# FrontPannel.net
KiCad netlist of a schematic drawn in Altium Designer
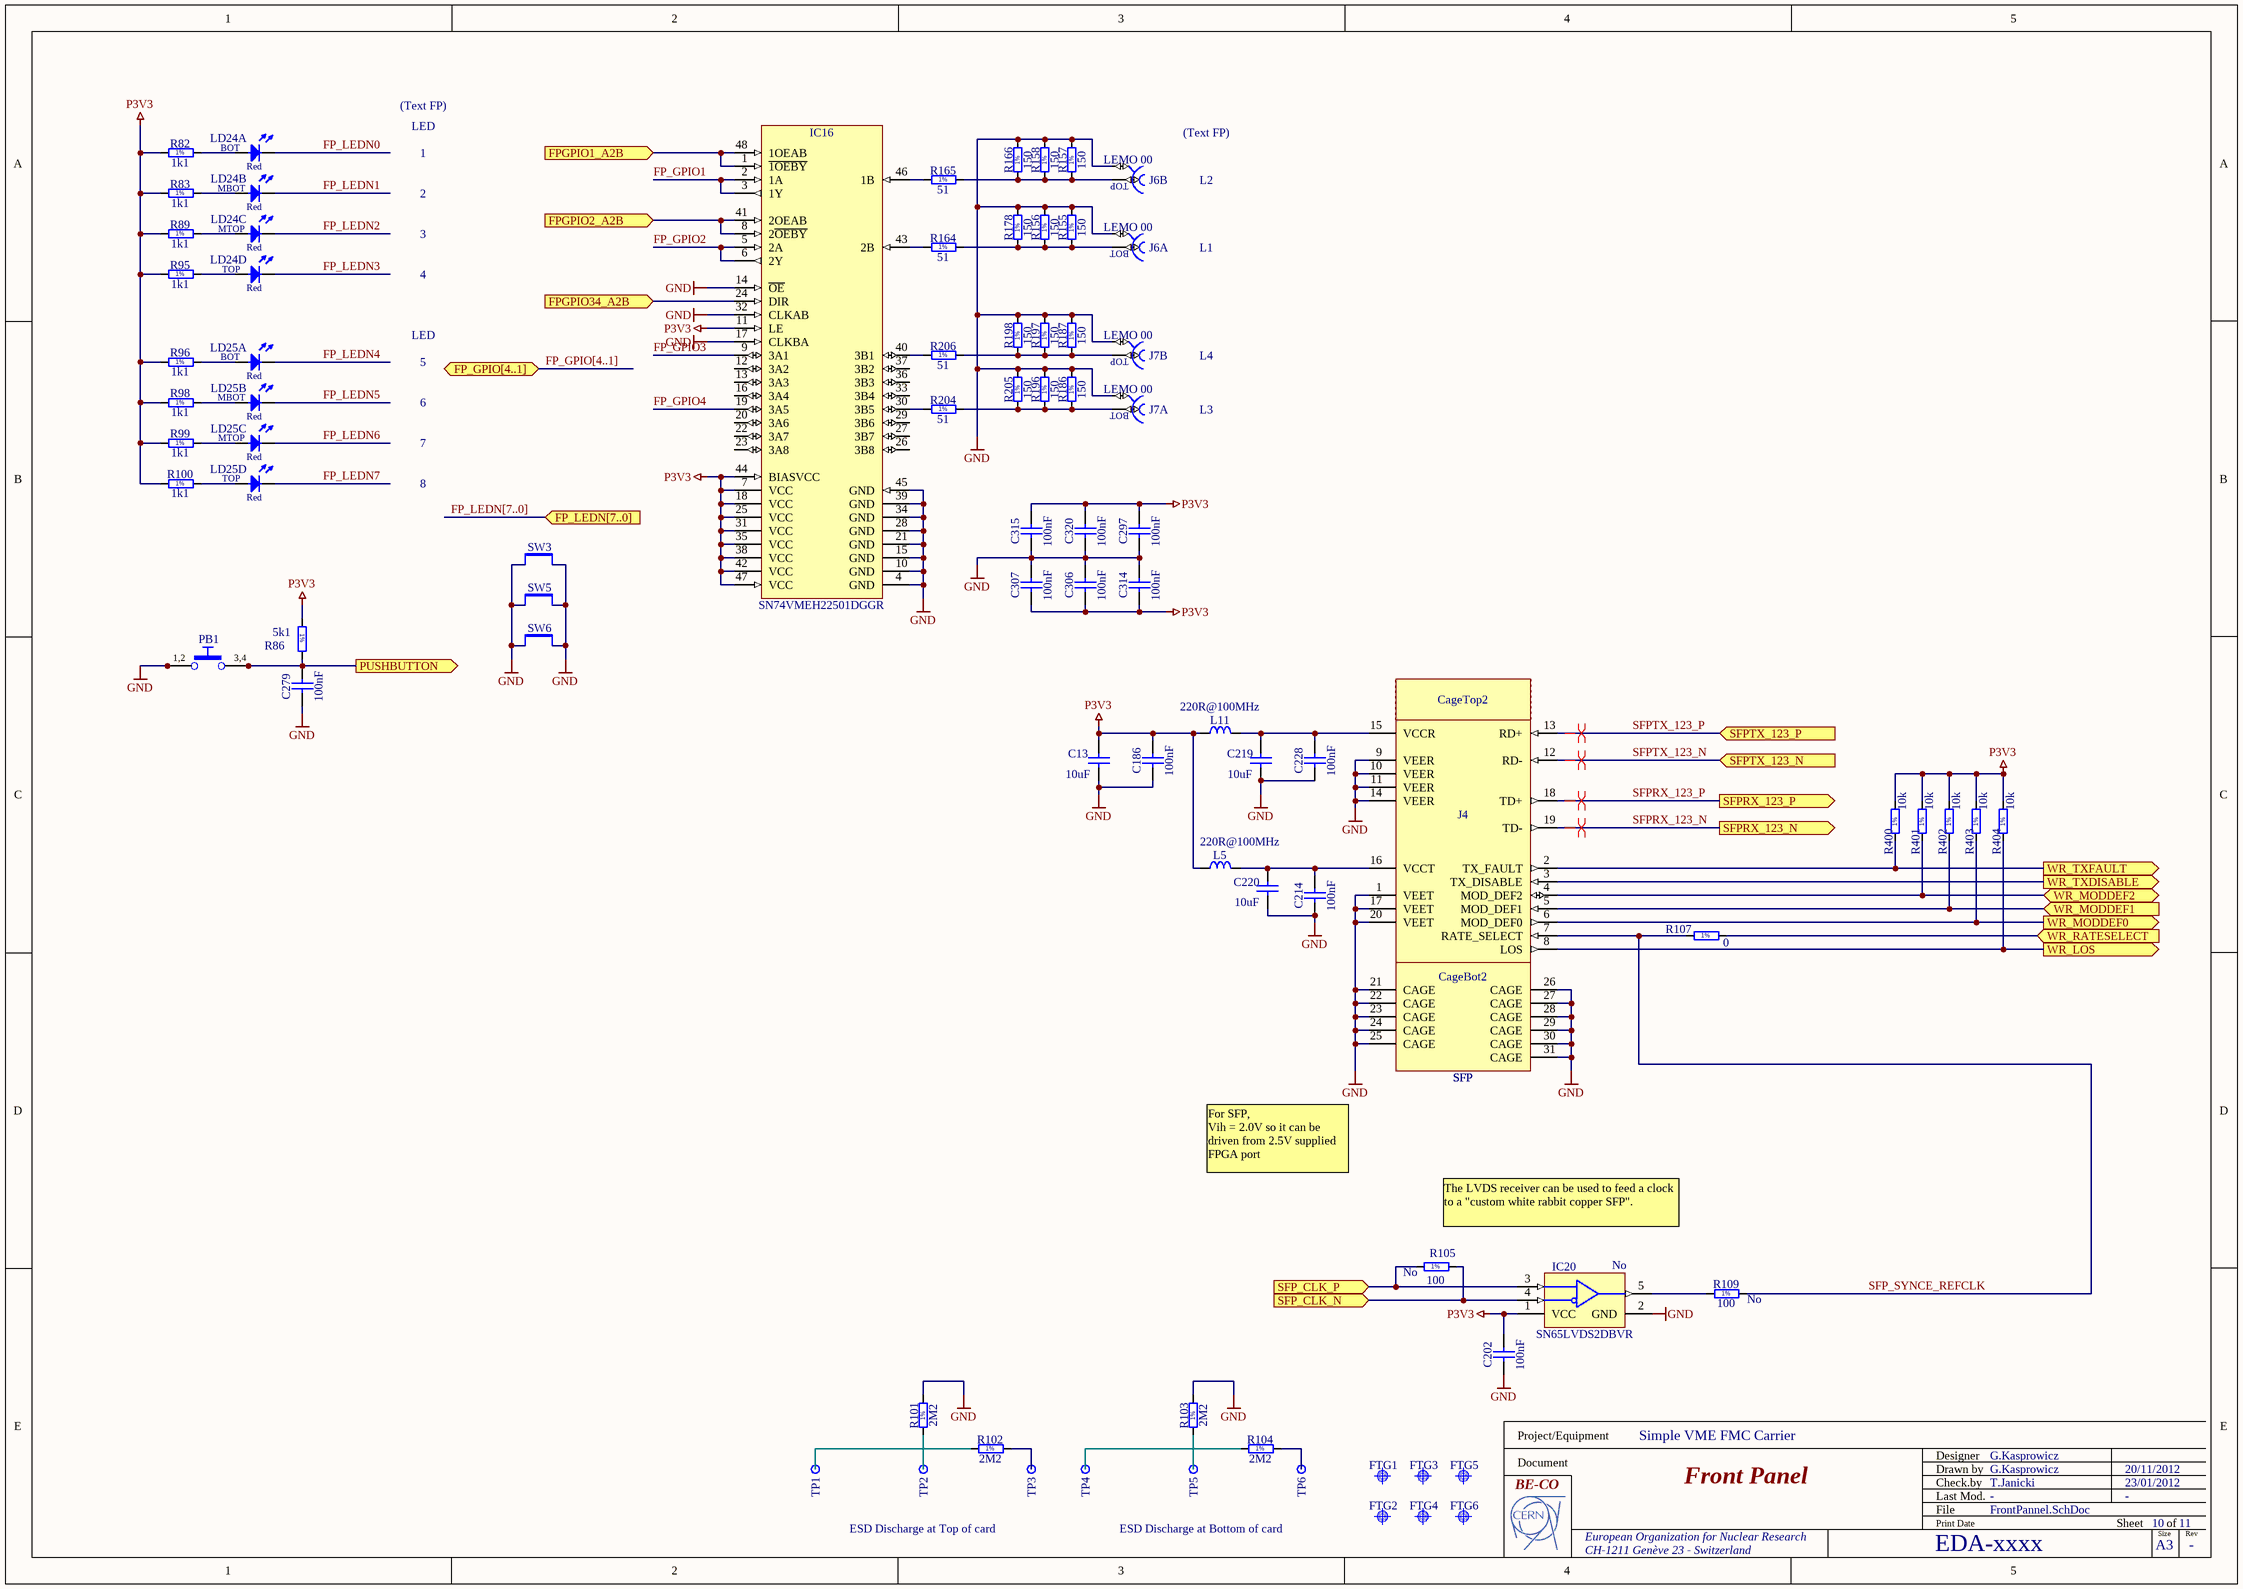
[diagram p0: FrontPannel.SchDoc]

(export (version "E")
  (design (tool "Eeschema 10.0.6"))
  (components
    (comp (ref "C13")
      (value "10uF")
      (footprint "CAPC3225X270N")
      (description "Non-polarised capacitor")
      (fields
        (field (name "PART NUMBER") "CC1210_10UF_25V_10%_X7R")
        (field (name "VOLTAGE") "25V")
        (field (name "AUTHOR") "CERN DEM JLC")
      )
      (libsource (lib "Capacitors") (part "Capacitor - non polarized"))
    )
    (comp (ref "C186")
      (value "100nF")
      (footprint "CAPC1005X55N")
      (description "Non-polarised capacitor")
      (fields
        (field (name "PART NUMBER") "CC0402_100NF_16V_10%_X7R")
        (field (name "VOLTAGE") "16V")
        (field (name "AUTHOR") "CERN DEM JLC")
      )
      (libsource (lib "Capacitors") (part "Capacitor - non polarized"))
    )
    (comp (ref "C202")
      (value "100nF")
      (footprint "CAPC1005X55N")
      (description "Non-polarised capacitor")
      (fields
        (field (name "PART NUMBER") "CC0402_100NF_16V_10%_X7R")
        (field (name "VOLTAGE") "16V")
        (field (name "AUTHOR") "CERN DEM JLC")
      )
      (libsource (lib "Capacitors") (part "Capacitor - non polarized"))
    )
    (comp (ref "C214")
      (value "100nF")
      (footprint "CAPC1005X55N")
      (description "Non-polarised capacitor")
      (fields
        (field (name "PART NUMBER") "CC0402_100NF_16V_10%_X7R")
        (field (name "VOLTAGE") "16V")
        (field (name "AUTHOR") "CERN DEM JLC")
      )
      (libsource (lib "Capacitors") (part "Capacitor - non polarized"))
    )
    (comp (ref "C219")
      (value "10uF")
      (footprint "CAPC3225X270N")
      (description "Non-polarised capacitor")
      (fields
        (field (name "PART NUMBER") "CC1210_10UF_25V_10%_X7R")
        (field (name "VOLTAGE") "25V")
        (field (name "AUTHOR") "CERN DEM JLC")
      )
      (libsource (lib "Capacitors") (part "Capacitor - non polarized"))
    )
    (comp (ref "C220")
      (value "10uF")
      (footprint "CAPC3225X270N")
      (description "Non-polarised capacitor")
      (fields
        (field (name "PART NUMBER") "CC1210_10UF_25V_10%_X7R")
        (field (name "VOLTAGE") "25V")
        (field (name "AUTHOR") "CERN DEM JLC")
      )
      (libsource (lib "Capacitors") (part "Capacitor - non polarized"))
    )
    (comp (ref "C228")
      (value "100nF")
      (footprint "CAPC1005X55N")
      (description "Non-polarised capacitor")
      (fields
        (field (name "PART NUMBER") "CC0402_100NF_16V_10%_X7R")
        (field (name "VOLTAGE") "16V")
        (field (name "AUTHOR") "CERN DEM JLC")
      )
      (libsource (lib "Capacitors") (part "Capacitor - non polarized"))
    )
    (comp (ref "C279")
      (value "100nF")
      (footprint "CAPC1005X55N")
      (description "Non-polarised capacitor")
      (fields
        (field (name "PART NUMBER") "CC0402_100NF_16V_10%_X7R")
        (field (name "VOLTAGE") "16V")
        (field (name "AUTHOR") "CERN DEM JLC")
      )
      (libsource (lib "Capacitors") (part "Capacitor - non polarized"))
    )
    (comp (ref "C297")
      (value "100nF")
      (footprint "CAPC1005X55N")
      (description "Non-polarised capacitor")
      (fields
        (field (name "PART NUMBER") "CC0402_100NF_16V_10%_X7R")
        (field (name "VOLTAGE") "16V")
        (field (name "AUTHOR") "CERN DEM JLC")
      )
      (libsource (lib "Capacitors") (part "Capacitor - non polarized"))
    )
    (comp (ref "C306")
      (value "100nF")
      (footprint "CAPC1005X55N")
      (description "Non-polarised capacitor")
      (fields
        (field (name "PART NUMBER") "CC0402_100NF_16V_10%_X7R")
        (field (name "VOLTAGE") "16V")
        (field (name "AUTHOR") "CERN DEM JLC")
      )
      (libsource (lib "Capacitors") (part "Capacitor - non polarized"))
    )
    (comp (ref "C307")
      (value "100nF")
      (footprint "CAPC1005X55N")
      (description "Non-polarised capacitor")
      (fields
        (field (name "PART NUMBER") "CC0402_100NF_16V_10%_X7R")
        (field (name "VOLTAGE") "16V")
        (field (name "AUTHOR") "CERN DEM JLC")
      )
      (libsource (lib "Capacitors") (part "Capacitor - non polarized"))
    )
    (comp (ref "C314")
      (value "100nF")
      (footprint "CAPC1005X55N")
      (description "Non-polarised capacitor")
      (fields
        (field (name "PART NUMBER") "CC0402_100NF_16V_10%_X7R")
        (field (name "VOLTAGE") "16V")
        (field (name "AUTHOR") "CERN DEM JLC")
      )
      (libsource (lib "Capacitors") (part "Capacitor - non polarized"))
    )
    (comp (ref "C315")
      (value "100nF")
      (footprint "CAPC1005X55N")
      (description "Non-polarised capacitor")
      (fields
        (field (name "PART NUMBER") "CC0402_100NF_16V_10%_X7R")
        (field (name "VOLTAGE") "16V")
        (field (name "AUTHOR") "CERN DEM JLC")
      )
      (libsource (lib "Capacitors") (part "Capacitor - non polarized"))
    )
    (comp (ref "C320")
      (value "100nF")
      (footprint "CAPC1005X55N")
      (description "Non-polarised capacitor")
      (fields
        (field (name "PART NUMBER") "CC0402_100NF_16V_10%_X7R")
        (field (name "VOLTAGE") "16V")
        (field (name "AUTHOR") "CERN DEM JLC")
      )
      (libsource (lib "Capacitors") (part "Capacitor - non polarized"))
    )
    (comp (ref "CageBot2")
      (value "SFP")
      (footprint "TYCO_6367034-1")
      (description "SFP  Cage Bottom (Small Form-factor Pluggable)")
      (fields
        (field (name "PART NUMBER") "TYCO_6367034-1")
        (field (name "MANUFACTURER") "TYCO ELECTRONICS")
        (field (name "AUTHOR") "CERN DEM JLC")
      )
      (libsource (lib "Connectors") (part "SFPx1_Cage Bottom"))
    )
    (comp (ref "CageTop2")
      (value "SFP")
      (footprint "TYCO_6367035-1")
      (description "SFP  Cage Top (Small Form-factor Pluggable)")
      (fields
        (field (name "PART NUMBER") "TYCO_6367035-1")
        (field (name "MANUFACTURER") "TYCO ELECTRONICS")
        (field (name "AUTHOR") "CERN DEM JLC")
      )
      (libsource (lib "Connectors") (part "SFPx1_Cage Top"))
    )
    (comp (ref "FTG1")
      (value "Use only in PCB")
      (footprint "FIDUCIAL_TOP_S100-200")
      (description "Fiducial Target")
      (fields (field (name "PART NUMBER") "FIDUCIAL_TARGET_S100-200") (field (name "AUTHOR") "CERN DEM JLC"))
      (libsource (lib "Eletro-mechanical") (part "Fiducial Target"))
    )
    (comp (ref "FTG2")
      (value "Use only in PCB")
      (footprint "FIDUCIAL_TOP_S100-200")
      (description "Fiducial Target")
      (fields (field (name "PART NUMBER") "FIDUCIAL_TARGET_S100-200") (field (name "AUTHOR") "CERN DEM JLC"))
      (libsource (lib "Eletro-mechanical") (part "Fiducial Target"))
    )
    (comp (ref "FTG3")
      (value "Use only in PCB")
      (footprint "FIDUCIAL_TOP_S100-200")
      (description "Fiducial Target")
      (fields (field (name "PART NUMBER") "FIDUCIAL_TARGET_S100-200") (field (name "AUTHOR") "CERN DEM JLC"))
      (libsource (lib "Eletro-mechanical") (part "Fiducial Target"))
    )
    (comp (ref "FTG4")
      (value "Use only in PCB")
      (footprint "FIDUCIAL_TOP_S100-200")
      (description "Fiducial Target")
      (fields (field (name "PART NUMBER") "FIDUCIAL_TARGET_S100-200") (field (name "AUTHOR") "CERN DEM JLC"))
      (libsource (lib "Eletro-mechanical") (part "Fiducial Target"))
    )
    (comp (ref "FTG5")
      (value "Use only in PCB")
      (footprint "FIDUCIAL_TOP_S100-200")
      (description "Fiducial Target")
      (fields (field (name "PART NUMBER") "FIDUCIAL_TARGET_S100-200") (field (name "AUTHOR") "CERN DEM JLC"))
      (libsource (lib "Eletro-mechanical") (part "Fiducial Target"))
    )
    (comp (ref "FTG6")
      (value "Use only in PCB")
      (footprint "FIDUCIAL_TOP_S100-200")
      (description "Fiducial Target")
      (fields (field (name "PART NUMBER") "FIDUCIAL_TARGET_S100-200") (field (name "AUTHOR") "CERN DEM JLC"))
      (libsource (lib "Eletro-mechanical") (part "Fiducial Target"))
    )
    (comp (ref "IC16")
      (value "SN74VMEH22501DGGR")
      (footprint "SOP50P810X120-48N")
      (description "8-Bit Universal Bus Transceiver and Two 1-Bit Bus Transceivers with 3-State Outputs")
      (fields (field (name "MANUFACTURER") "TEXAS INSTRUMENTS") (field (name "AUTHOR") "CERN DEM JLC"))
      (libsource (lib "ICs And Semiconductors") (part "74VMEH22501"))
    )
    (comp (ref "IC20")
      (value "SN65LVDS2DBVR")
      (footprint "SOT95P280X145-5N")
      (description "High-Speed Differential Line Receiver")
      (fields
        (field (name "MANUFACTURER") "TEXAS INSTRUMENTS")
        (field (name "MOUNTED") "No")
        (field (name "AUTHOR") "CERN DEM JLC")
      )
      (libsource (lib "ICs And Semiconductors") (part "SN65LVDS2DBVR"))
    )
    (comp (ref "J4")
      (value "SFP")
      (footprint "TYCO_1367073-1")
      (description "20 Position SFP  Connector (Small Form-factor Pluggable)")
      (fields
        (field (name "PART NUMBER") "TYCO_1367073-1")
        (field (name "MANUFACTURER") "TYCO ELECTRONICS")
        (field (name "AUTHOR") "CERN DEM JLC")
      )
      (libsource (lib "Connectors") (part "SFPx1"))
    )
    (comp (ref "J6")
      (value "LEMO 00")
      (footprint "LEMO_EPY.00.250.NTNY")
      (description "Dual Female Coax 1-2 Common Shield 3")
      (fields
        (field (name "PART NUMBER") "LEMO_EPY.00.250.NTNY")
        (field (name "MANUFACTURER") "LEMO")
        (field (name "AUTHOR") "CERN DEM JLC")
      )
      (libsource (lib "Connectors") (part "LEMO_EPY.00.250.NTN"))
    )
    (comp (ref "J7")
      (value "LEMO 00")
      (footprint "LEMO_EPY.00.250.NTNY")
      (description "Dual Female Coax 1-2 Common Shield 3")
      (fields
        (field (name "PART NUMBER") "LEMO_EPY.00.250.NTNY")
        (field (name "MANUFACTURER") "LEMO")
        (field (name "AUTHOR") "CERN DEM JLC")
      )
      (libsource (lib "Connectors") (part "LEMO_EPY.00.250.NTN"))
    )
    (comp (ref "L5")
      (value "220R@100MHz")
      (footprint "INDC2012X105N")
      (description "Inductor")
      (fields
        (field (name "PART NUMBER") "IND0805_MURATA_BLM21PG221SN1D")
        (field (name "POWER") "2A")
        (field (name "AUTHOR") "CERN DEM JLC")
      )
      (libsource (lib "Inductors & Transformers") (part "Inductor"))
    )
    (comp (ref "L11")
      (value "220R@100MHz")
      (footprint "INDC2012X105N")
      (description "Inductor")
      (fields
        (field (name "PART NUMBER") "IND0805_MURATA_BLM21PG221SN1D")
        (field (name "POWER") "2A")
        (field (name "AUTHOR") "CERN DEM JLC")
      )
      (libsource (lib "Inductors & Transformers") (part "Inductor"))
    )
    (comp (ref "LD24")
      (value "HE Red")
      (footprint "LED_BIVAR_H485CHDL")
      (description "LED x4 Red 1C2A-BOT_3C4A_5C6A_7C8A-TOP")
      (fields
        (field (name "PART NUMBER") "LED_BIVAR_H485CHDL")
        (field (name "MANUFACTURER") "BIVAR")
        (field (name "AUTHOR") "CERN DEM JLC")
      )
      (libsource (lib "ICs And Semiconductors") (part "LED x4 Red 1C2A-BOT_3C4A_5C6A_7C8A-TOP"))
    )
    (comp (ref "LD25")
      (value "HE Red")
      (footprint "LED_BIVAR_H485CHDL")
      (description "LED x4 Red 1C2A-BOT_3C4A_5C6A_7C8A-TOP")
      (fields
        (field (name "PART NUMBER") "LED_BIVAR_H485CHDL")
        (field (name "MANUFACTURER") "BIVAR")
        (field (name "AUTHOR") "CERN DEM JLC")
      )
      (libsource (lib "ICs And Semiconductors") (part "LED x4 Red 1C2A-BOT_3C4A_5C6A_7C8A-TOP"))
    )
    (comp (ref "PB1")
      (value "Push Button")
      (footprint "PB_TYCO_ALCOSWITCH_FSM2JSMA")
      (description "Push-Button Switch SPDT")
      (fields
        (field (name "PART NUMBER") "PB_TYCO_ALCOSWITCH_FSM2JSMA")
        (field (name "MANUFACTURER") "TYCO ALCOSWITCH")
        (field (name "AUTHOR") "CERN DEM JLC")
      )
      (libsource (lib "Eletro-mechanical") (part "PB SPST 12NO-34NO"))
    )
    (comp (ref "R82")
      (value "1k1")
      (footprint "RESC1608X55N")
      (description "Resistor - 1%")
      (fields
        (field (name "PART NUMBER") "R0603_1K1_1%_0.1W_100PPM")
        (field (name "POWER") "0.1W")
        (field (name "AUTHOR") "CERN DEM JLC")
      )
      (libsource (lib "Resistors") (part "Resistor - 1%"))
    )
    (comp (ref "R83")
      (value "1k1")
      (footprint "RESC1608X55N")
      (description "Resistor - 1%")
      (fields
        (field (name "PART NUMBER") "R0603_1K1_1%_0.1W_100PPM")
        (field (name "POWER") "0.1W")
        (field (name "AUTHOR") "CERN DEM JLC")
      )
      (libsource (lib "Resistors") (part "Resistor - 1%"))
    )
    (comp (ref "R86")
      (value "5k1")
      (footprint "RESC1608X55N")
      (description "Resistor - 1%")
      (fields
        (field (name "PART NUMBER") "R0603_5K1_1%_0.1W_100PPM")
        (field (name "POWER") "0.1W")
        (field (name "AUTHOR") "CERN DEM JLC")
      )
      (libsource (lib "Resistors") (part "Resistor - 1%"))
    )
    (comp (ref "R89")
      (value "1k1")
      (footprint "RESC1608X55N")
      (description "Resistor - 1%")
      (fields
        (field (name "PART NUMBER") "R0603_1K1_1%_0.1W_100PPM")
        (field (name "POWER") "0.1W")
        (field (name "AUTHOR") "CERN DEM JLC")
      )
      (libsource (lib "Resistors") (part "Resistor - 1%"))
    )
    (comp (ref "R95")
      (value "1k1")
      (footprint "RESC1608X55N")
      (description "Resistor - 1%")
      (fields
        (field (name "PART NUMBER") "R0603_1K1_1%_0.1W_100PPM")
        (field (name "POWER") "0.1W")
        (field (name "AUTHOR") "CERN DEM JLC")
      )
      (libsource (lib "Resistors") (part "Resistor - 1%"))
    )
    (comp (ref "R96")
      (value "1k1")
      (footprint "RESC1608X55N")
      (description "Resistor - 1%")
      (fields
        (field (name "PART NUMBER") "R0603_1K1_1%_0.1W_100PPM")
        (field (name "POWER") "0.1W")
        (field (name "AUTHOR") "CERN DEM JLC")
      )
      (libsource (lib "Resistors") (part "Resistor - 1%"))
    )
    (comp (ref "R98")
      (value "1k1")
      (footprint "RESC1608X55N")
      (description "Resistor - 1%")
      (fields
        (field (name "PART NUMBER") "R0603_1K1_1%_0.1W_100PPM")
        (field (name "POWER") "0.1W")
        (field (name "AUTHOR") "CERN DEM JLC")
      )
      (libsource (lib "Resistors") (part "Resistor - 1%"))
    )
    (comp (ref "R99")
      (value "1k1")
      (footprint "RESC1608X55N")
      (description "Resistor - 1%")
      (fields
        (field (name "PART NUMBER") "R0603_1K1_1%_0.1W_100PPM")
        (field (name "POWER") "0.1W")
        (field (name "AUTHOR") "CERN DEM JLC")
      )
      (libsource (lib "Resistors") (part "Resistor - 1%"))
    )
    (comp (ref "R100")
      (value "1k1")
      (footprint "RESC1608X55N")
      (description "Resistor - 1%")
      (fields
        (field (name "PART NUMBER") "R0603_1K1_1%_0.1W_100PPM")
        (field (name "POWER") "0.1W")
        (field (name "AUTHOR") "CERN DEM JLC")
      )
      (libsource (lib "Resistors") (part "Resistor - 1%"))
    )
    (comp (ref "R101")
      (value "2M2")
      (footprint "RESC2012X60N")
      (description "Resistor - 1%")
      (fields
        (field (name "PART NUMBER") "R0805_2M2_1%_0.125W_100PPM")
        (field (name "POWER") "0.125W")
        (field (name "AUTHOR") "CERN DEM JLC")
      )
      (libsource (lib "Resistors") (part "Resistor - 1%"))
    )
    (comp (ref "R102")
      (value "2M2")
      (footprint "RESC2012X60N")
      (description "Resistor - 1%")
      (fields
        (field (name "PART NUMBER") "R0805_2M2_1%_0.125W_100PPM")
        (field (name "POWER") "0.125W")
        (field (name "AUTHOR") "CERN DEM JLC")
      )
      (libsource (lib "Resistors") (part "Resistor - 1%"))
    )
    (comp (ref "R103")
      (value "2M2")
      (footprint "RESC2012X60N")
      (description "Resistor - 1%")
      (fields
        (field (name "PART NUMBER") "R0805_2M2_1%_0.125W_100PPM")
        (field (name "POWER") "0.125W")
        (field (name "AUTHOR") "CERN DEM JLC")
      )
      (libsource (lib "Resistors") (part "Resistor - 1%"))
    )
    (comp (ref "R104")
      (value "2M2")
      (footprint "RESC2012X60N")
      (description "Resistor - 1%")
      (fields
        (field (name "PART NUMBER") "R0805_2M2_1%_0.125W_100PPM")
        (field (name "POWER") "0.125W")
        (field (name "AUTHOR") "CERN DEM JLC")
      )
      (libsource (lib "Resistors") (part "Resistor - 1%"))
    )
    (comp (ref "R105")
      (value "100")
      (footprint "RESC1608X55N")
      (description "Resistor - 1%")
      (fields
        (field (name "PART NUMBER") "R0603_100R_1%_0.1W_100PPM")
        (field (name "POWER") "0.1W")
        (field (name "MOUNTED") "No")
        (field (name "AUTHOR") "CERN DEM JLC")
      )
      (libsource (lib "Resistors") (part "Resistor - 1%"))
    )
    (comp (ref "R107")
      (value "0")
      (footprint "RESC1608X55N")
      (description "Resistor - 1%")
      (fields
        (field (name "PART NUMBER") "R0603_0R_JUMPER")
        (field (name "MANUFACTURER") "GENERIC")
        (field (name "AUTHOR") "CERN DEM JLC")
      )
      (libsource (lib "Resistors") (part "Resistor - 1%"))
    )
    (comp (ref "R109")
      (value "100")
      (footprint "RESC1608X55N")
      (description "Resistor - 1%")
      (fields
        (field (name "PART NUMBER") "R0603_100R_1%_0.1W_100PPM")
        (field (name "POWER") "0.1W")
        (field (name "MOUNTED") "No")
        (field (name "AUTHOR") "CERN DEM JLC")
      )
      (libsource (lib "Resistors") (part "Resistor - 1%"))
    )
    (comp (ref "R155")
      (value "150")
      (footprint "RESC1005X40N")
      (description "Resistor - 1%")
      (fields
        (field (name "PART NUMBER") "R0402_150R_1%_0.0625W_100PPM")
        (field (name "POWER") "0.0625W")
        (field (name "AUTHOR") "CERN DEM JLC")
      )
      (libsource (lib "Resistors") (part "Resistor - 1%"))
    )
    (comp (ref "R156")
      (value "150")
      (footprint "RESC1005X40N")
      (description "Resistor - 1%")
      (fields
        (field (name "PART NUMBER") "R0402_150R_1%_0.0625W_100PPM")
        (field (name "POWER") "0.0625W")
        (field (name "AUTHOR") "CERN DEM JLC")
      )
      (libsource (lib "Resistors") (part "Resistor - 1%"))
    )
    (comp (ref "R157")
      (value "150")
      (footprint "RESC1005X40N")
      (description "Resistor - 1%")
      (fields
        (field (name "PART NUMBER") "R0402_150R_1%_0.0625W_100PPM")
        (field (name "POWER") "0.0625W")
        (field (name "AUTHOR") "CERN DEM JLC")
      )
      (libsource (lib "Resistors") (part "Resistor - 1%"))
    )
    (comp (ref "R158")
      (value "150")
      (footprint "RESC1005X40N")
      (description "Resistor - 1%")
      (fields
        (field (name "PART NUMBER") "R0402_150R_1%_0.0625W_100PPM")
        (field (name "POWER") "0.0625W")
        (field (name "AUTHOR") "CERN DEM JLC")
      )
      (libsource (lib "Resistors") (part "Resistor - 1%"))
    )
    (comp (ref "R164")
      (value "51")
      (footprint "RESC1005X40N")
      (description "Resistor - 1%")
      (fields
        (field (name "PART NUMBER") "R0402_51R_1%_0.0625W_100PPM")
        (field (name "POWER") "0.0625W")
        (field (name "AUTHOR") "CERN DEM JLC")
      )
      (libsource (lib "Resistors") (part "Resistor - 1%"))
    )
    (comp (ref "R165")
      (value "51")
      (footprint "RESC1005X40N")
      (description "Resistor - 1%")
      (fields
        (field (name "PART NUMBER") "R0402_51R_1%_0.0625W_100PPM")
        (field (name "POWER") "0.0625W")
        (field (name "AUTHOR") "CERN DEM JLC")
      )
      (libsource (lib "Resistors") (part "Resistor - 1%"))
    )
    (comp (ref "R166")
      (value "150")
      (footprint "RESC1005X40N")
      (description "Resistor - 1%")
      (fields
        (field (name "PART NUMBER") "R0402_150R_1%_0.0625W_100PPM")
        (field (name "POWER") "0.0625W")
        (field (name "AUTHOR") "CERN DEM JLC")
      )
      (libsource (lib "Resistors") (part "Resistor - 1%"))
    )
    (comp (ref "R178")
      (value "150")
      (footprint "RESC1005X40N")
      (description "Resistor - 1%")
      (fields
        (field (name "PART NUMBER") "R0402_150R_1%_0.0625W_100PPM")
        (field (name "POWER") "0.0625W")
        (field (name "AUTHOR") "CERN DEM JLC")
      )
      (libsource (lib "Resistors") (part "Resistor - 1%"))
    )
    (comp (ref "R186")
      (value "150")
      (footprint "RESC1005X40N")
      (description "Resistor - 1%")
      (fields
        (field (name "PART NUMBER") "R0402_150R_1%_0.0625W_100PPM")
        (field (name "POWER") "0.0625W")
        (field (name "AUTHOR") "CERN DEM JLC")
      )
      (libsource (lib "Resistors") (part "Resistor - 1%"))
    )
    (comp (ref "R187")
      (value "150")
      (footprint "RESC1005X40N")
      (description "Resistor - 1%")
      (fields
        (field (name "PART NUMBER") "R0402_150R_1%_0.0625W_100PPM")
        (field (name "POWER") "0.0625W")
        (field (name "AUTHOR") "CERN DEM JLC")
      )
      (libsource (lib "Resistors") (part "Resistor - 1%"))
    )
    (comp (ref "R196")
      (value "150")
      (footprint "RESC1005X40N")
      (description "Resistor - 1%")
      (fields
        (field (name "PART NUMBER") "R0402_150R_1%_0.0625W_100PPM")
        (field (name "POWER") "0.0625W")
        (field (name "AUTHOR") "CERN DEM JLC")
      )
      (libsource (lib "Resistors") (part "Resistor - 1%"))
    )
    (comp (ref "R197")
      (value "150")
      (footprint "RESC1005X40N")
      (description "Resistor - 1%")
      (fields
        (field (name "PART NUMBER") "R0402_150R_1%_0.0625W_100PPM")
        (field (name "POWER") "0.0625W")
        (field (name "AUTHOR") "CERN DEM JLC")
      )
      (libsource (lib "Resistors") (part "Resistor - 1%"))
    )
    (comp (ref "R198")
      (value "150")
      (footprint "RESC1005X40N")
      (description "Resistor - 1%")
      (fields
        (field (name "PART NUMBER") "R0402_150R_1%_0.0625W_100PPM")
        (field (name "POWER") "0.0625W")
        (field (name "AUTHOR") "CERN DEM JLC")
      )
      (libsource (lib "Resistors") (part "Resistor - 1%"))
    )
    (comp (ref "R204")
      (value "51")
      (footprint "RESC1005X40N")
      (description "Resistor - 1%")
      (fields
        (field (name "PART NUMBER") "R0402_51R_1%_0.0625W_100PPM")
        (field (name "POWER") "0.0625W")
        (field (name "AUTHOR") "CERN DEM JLC")
      )
      (libsource (lib "Resistors") (part "Resistor - 1%"))
    )
    (comp (ref "R205")
      (value "150")
      (footprint "RESC1005X40N")
      (description "Resistor - 1%")
      (fields
        (field (name "PART NUMBER") "R0402_150R_1%_0.0625W_100PPM")
        (field (name "POWER") "0.0625W")
        (field (name "AUTHOR") "CERN DEM JLC")
      )
      (libsource (lib "Resistors") (part "Resistor - 1%"))
    )
    (comp (ref "R206")
      (value "51")
      (footprint "RESC1005X40N")
      (description "Resistor - 1%")
      (fields
        (field (name "PART NUMBER") "R0402_51R_1%_0.0625W_100PPM")
        (field (name "POWER") "0.0625W")
        (field (name "AUTHOR") "CERN DEM JLC")
      )
      (libsource (lib "Resistors") (part "Resistor - 1%"))
    )
    (comp (ref "R400")
      (value "10k")
      (footprint "RESC1608X55N")
      (description "Resistor - 1%")
      (fields
        (field (name "PART NUMBER") "R0603_10K_1%_0.1W_100PPM")
        (field (name "POWER") "0.1W")
        (field (name "AUTHOR") "CERN DEM JLC")
      )
      (libsource (lib "Resistors") (part "Resistor - 1%"))
    )
    (comp (ref "R401")
      (value "10k")
      (footprint "RESC1608X55N")
      (description "Resistor - 1%")
      (fields
        (field (name "PART NUMBER") "R0603_10K_1%_0.1W_100PPM")
        (field (name "POWER") "0.1W")
        (field (name "AUTHOR") "CERN DEM JLC")
      )
      (libsource (lib "Resistors") (part "Resistor - 1%"))
    )
    (comp (ref "R402")
      (value "10k")
      (footprint "RESC1608X55N")
      (description "Resistor - 1%")
      (fields
        (field (name "PART NUMBER") "R0603_10K_1%_0.1W_100PPM")
        (field (name "POWER") "0.1W")
        (field (name "AUTHOR") "CERN DEM JLC")
      )
      (libsource (lib "Resistors") (part "Resistor - 1%"))
    )
    (comp (ref "R403")
      (value "10k")
      (footprint "RESC1608X55N")
      (description "Resistor - 1%")
      (fields
        (field (name "PART NUMBER") "R0603_10K_1%_0.1W_100PPM")
        (field (name "POWER") "0.1W")
        (field (name "AUTHOR") "CERN DEM JLC")
      )
      (libsource (lib "Resistors") (part "Resistor - 1%"))
    )
    (comp (ref "R404")
      (value "10k")
      (footprint "RESC1608X55N")
      (description "Resistor - 1%")
      (fields
        (field (name "PART NUMBER") "R0603_10K_1%_0.1W_100PPM")
        (field (name "POWER") "0.1W")
        (field (name "AUTHOR") "CERN DEM JLC")
      )
      (libsource (lib "Resistors") (part "Resistor - 1%"))
    )
    (comp (ref "SW3")
      (value "Jumper Type2")
      (footprint "COMATEL_313.0004.0.00.500")
      (description "Jumper 2 pins")
      (fields
        (field (name "PART NUMBER") "COMATEL_313.0004.0.00.500")
        (field (name "MANUFACTURER") "KONTEK COMATEL")
        (field (name "AUTHOR") "CERN DEM JMW")
      )
      (libsource (lib "Connectors") (part "Jumper Type2"))
    )
    (comp (ref "SW5")
      (value "Jumper Type2")
      (footprint "COMATEL_313.0004.0.00.500")
      (description "Jumper 2 pins")
      (fields
        (field (name "PART NUMBER") "COMATEL_313.0004.0.00.500")
        (field (name "MANUFACTURER") "KONTEK COMATEL")
        (field (name "AUTHOR") "CERN DEM JMW")
      )
      (libsource (lib "Connectors") (part "Jumper Type2"))
    )
    (comp (ref "SW6")
      (value "Jumper Type2")
      (footprint "COMATEL_313.0004.0.00.500")
      (description "Jumper 2 pins")
      (fields
        (field (name "PART NUMBER") "COMATEL_313.0004.0.00.500")
        (field (name "MANUFACTURER") "KONTEK COMATEL")
        (field (name "AUTHOR") "CERN DEM JMW")
      )
      (libsource (lib "Connectors") (part "Jumper Type2"))
    )
    (comp (ref "TP1")
      (value "Test Point")
      (footprint "TPS127")
      (fields (field (name "PART NUMBER") "SMD_PAD_1.27X1.27MM") (field (name "AUTHOR") "CERN DEM JLC"))
      (libsource (lib "Eletro-mechanical") (part "Test Point"))
    )
    (comp (ref "TP2")
      (value "Test Point")
      (footprint "TPS127")
      (fields (field (name "PART NUMBER") "SMD_PAD_1.27X1.27MM") (field (name "AUTHOR") "CERN DEM JLC"))
      (libsource (lib "Eletro-mechanical") (part "Test Point"))
    )
    (comp (ref "TP3")
      (value "Test Point")
      (footprint "TPS127")
      (fields (field (name "PART NUMBER") "SMD_PAD_1.27X1.27MM") (field (name "AUTHOR") "CERN DEM JLC"))
      (libsource (lib "Eletro-mechanical") (part "Test Point"))
    )
    (comp (ref "TP4")
      (value "Test Point")
      (footprint "TPS127")
      (fields (field (name "PART NUMBER") "SMD_PAD_1.27X1.27MM") (field (name "AUTHOR") "CERN DEM JLC"))
      (libsource (lib "Eletro-mechanical") (part "Test Point"))
    )
    (comp (ref "TP5")
      (value "Test Point")
      (footprint "TPS127")
      (fields (field (name "PART NUMBER") "SMD_PAD_1.27X1.27MM") (field (name "AUTHOR") "CERN DEM JLC"))
      (libsource (lib "Eletro-mechanical") (part "Test Point"))
    )
    (comp (ref "TP6")
      (value "Test Point")
      (footprint "TPS127")
      (fields (field (name "PART NUMBER") "SMD_PAD_1.27X1.27MM") (field (name "AUTHOR") "CERN DEM JLC"))
      (libsource (lib "Eletro-mechanical") (part "Test Point"))
    )
  )
  (nets
    (net (code "1") (name "/FPGPIO1_A2B") (class "Default")
      (node (ref "IC16") (pin "1") (pinfunction "~{1OEBY}_1") (pintype "input"))
      (node (ref "IC16") (pin "48") (pinfunction "1OEAB_48") (pintype "input"))
    )
    (net (code "2") (name "/FPGPIO2_A2B") (class "Default")
      (node (ref "IC16") (pin "41") (pinfunction "2OEAB_41") (pintype "input"))
      (node (ref "IC16") (pin "8") (pinfunction "2~{OEBY}_8") (pintype "input"))
    )
    (net (code "3") (name "/FPGPIO34_A2B") (class "Default")
      (node (ref "IC16") (pin "24") (pinfunction "DIR_24") (pintype "input"))
    )
    (net (code "4") (name "/FP_GPIO1") (class "Default")
      (node (ref "IC16") (pin "2") (pinfunction "1A_2") (pintype "input"))
      (node (ref "IC16") (pin "3") (pinfunction "1Y_3") (pintype "output"))
    )
    (net (code "5") (name "/FP_GPIO2") (class "Default")
      (node (ref "IC16") (pin "5") (pinfunction "2A_5") (pintype "input"))
      (node (ref "IC16") (pin "6") (pinfunction "2Y_6") (pintype "output"))
    )
    (net (code "6") (name "/FP_GPIO3") (class "Default")
      (node (ref "IC16") (pin "9") (pinfunction "3A1_9") (pintype "bidirectional"))
    )
    (net (code "7") (name "/FP_GPIO4") (class "Default")
      (node (ref "IC16") (pin "19") (pinfunction "3A5_19") (pintype "bidirectional"))
    )
    (net (code "9") (name "/FP_LEDN0") (class "Default")
      (node (ref "LD24") (pin "1") (pinfunction "C_1") (pintype "passive"))
    )
    (net (code "10") (name "/FP_LEDN1") (class "Default")
      (node (ref "LD24") (pin "3") (pinfunction "C_3") (pintype "passive"))
    )
    (net (code "11") (name "/FP_LEDN2") (class "Default")
      (node (ref "LD24") (pin "5") (pinfunction "C_5") (pintype "passive"))
    )
    (net (code "12") (name "/FP_LEDN3") (class "Default")
      (node (ref "LD24") (pin "7") (pinfunction "C_7") (pintype "passive"))
    )
    (net (code "13") (name "/FP_LEDN4") (class "Default")
      (node (ref "LD25") (pin "1") (pinfunction "C_1") (pintype "passive"))
    )
    (net (code "14") (name "/FP_LEDN5") (class "Default")
      (node (ref "LD25") (pin "3") (pinfunction "C_3") (pintype "passive"))
    )
    (net (code "15") (name "/FP_LEDN6") (class "Default")
      (node (ref "LD25") (pin "5") (pinfunction "C_5") (pintype "passive"))
    )
    (net (code "16") (name "/FP_LEDN7") (class "Default")
      (node (ref "LD25") (pin "7") (pinfunction "C_7") (pintype "passive"))
    )
    (net (code "18") (name "/PUSHBUTTON") (class "Default")
      (node (ref "C279") (pin "2") (pinfunction "2_2") (pintype "passive"))
      (node (ref "PB1") (pin "3") (pinfunction "3_3") (pintype "passive"))
      (node (ref "PB1") (pin "4") (pinfunction "4_4") (pintype "passive"))
      (node (ref "R86") (pin "2") (pinfunction "2_2") (pintype "passive"))
    )
    (net (code "19") (name "/SFPRX_123_N") (class "Default")
      (node (ref "J4") (pin "19") (pinfunction "TD-_19") (pintype "output"))
    )
    (net (code "20") (name "/SFPRX_123_P") (class "Default")
      (node (ref "J4") (pin "18") (pinfunction "TD+_18") (pintype "output"))
    )
    (net (code "21") (name "/SFPTX_123_N") (class "Default")
      (node (ref "J4") (pin "12") (pinfunction "RD-_12") (pintype "input"))
    )
    (net (code "22") (name "/SFPTX_123_P") (class "Default")
      (node (ref "J4") (pin "13") (pinfunction "RD+_13") (pintype "input"))
    )
    (net (code "23") (name "/SFP_CLK_N") (class "Default")
      (node (ref "IC20") (pin "4") (pinfunction "B_4") (pintype "input"))
      (node (ref "R105") (pin "2") (pinfunction "2_2") (pintype "passive"))
    )
    (net (code "24") (name "/SFP_CLK_P") (class "Default")
      (node (ref "IC20") (pin "3") (pinfunction "A_3") (pintype "input"))
      (node (ref "R105") (pin "1") (pinfunction "1_1") (pintype "passive"))
    )
    (net (code "25") (name "/SFP_SYNCE_REFCLK") (class "Default")
      (node (ref "J4") (pin "7") (pinfunction "RATE_SELECT_7") (pintype "input"))
      (node (ref "R107") (pin "1") (pinfunction "1_1") (pintype "passive"))
      (node (ref "R109") (pin "2") (pinfunction "2_2") (pintype "passive"))
    )
    (net (code "26") (name "/WR_LOS") (class "Default")
      (node (ref "J4") (pin "8") (pinfunction "LOS_8") (pintype "output"))
      (node (ref "R404") (pin "1") (pinfunction "1_1") (pintype "passive"))
    )
    (net (code "27") (name "/WR_MODDEF0") (class "Default")
      (node (ref "J4") (pin "6") (pinfunction "MOD_DEF0_6") (pintype "output"))
      (node (ref "R403") (pin "1") (pinfunction "1_1") (pintype "passive"))
    )
    (net (code "28") (name "/WR_MODDEF1") (class "Default")
      (node (ref "J4") (pin "5") (pinfunction "MOD_DEF1_5") (pintype "input"))
      (node (ref "R402") (pin "1") (pinfunction "1_1") (pintype "passive"))
    )
    (net (code "29") (name "/WR_MODDEF2") (class "Default")
      (node (ref "J4") (pin "4") (pinfunction "MOD_DEF2_4") (pintype "bidirectional"))
      (node (ref "R401") (pin "1") (pinfunction "1_1") (pintype "passive"))
    )
    (net (code "30") (name "/WR_RATESELECT") (class "Default")
      (node (ref "R107") (pin "2") (pinfunction "2_2") (pintype "passive"))
    )
    (net (code "31") (name "/WR_TXDISABLE") (class "Default")
      (node (ref "J4") (pin "3") (pinfunction "TX_DISABLE_3") (pintype "input"))
    )
    (net (code "32") (name "/WR_TXFAULT") (class "Default")
      (node (ref "J4") (pin "2") (pinfunction "TX_FAULT_2") (pintype "output"))
      (node (ref "R400") (pin "1") (pinfunction "1_1") (pintype "passive"))
    )
    (net (code "33") (name "GND") (class "Default")
      (node (ref "C13") (pin "2") (pinfunction "2_2") (pintype "passive"))
      (node (ref "C186") (pin "2") (pinfunction "2_2") (pintype "passive"))
      (node (ref "C202") (pin "1") (pinfunction "1_1") (pintype "passive"))
      (node (ref "C214") (pin "2") (pinfunction "2_2") (pintype "passive"))
      (node (ref "C219") (pin "2") (pinfunction "2_2") (pintype "passive"))
      (node (ref "C220") (pin "2") (pinfunction "2_2") (pintype "passive"))
      (node (ref "C228") (pin "2") (pinfunction "2_2") (pintype "passive"))
      (node (ref "C279") (pin "1") (pinfunction "1_1") (pintype "passive"))
      (node (ref "C297") (pin "1") (pinfunction "1_1") (pintype "passive"))
      (node (ref "C306") (pin "2") (pinfunction "2_2") (pintype "passive"))
      (node (ref "C307") (pin "2") (pinfunction "2_2") (pintype "passive"))
      (node (ref "C314") (pin "2") (pinfunction "2_2") (pintype "passive"))
      (node (ref "C315") (pin "1") (pinfunction "1_1") (pintype "passive"))
      (node (ref "C320") (pin "1") (pinfunction "1_1") (pintype "passive"))
      (node (ref "CageBot2") (pin "21") (pinfunction "CAGE_21") (pintype "power_in"))
      (node (ref "CageBot2") (pin "22") (pinfunction "CAGE_22") (pintype "power_in"))
      (node (ref "CageBot2") (pin "23") (pinfunction "CAGE_23") (pintype "power_in"))
      (node (ref "CageBot2") (pin "24") (pinfunction "CAGE_24") (pintype "power_in"))
      (node (ref "CageBot2") (pin "25") (pinfunction "CAGE_25") (pintype "power_in"))
      (node (ref "CageBot2") (pin "26") (pinfunction "CAGE_26") (pintype "power_in"))
      (node (ref "CageBot2") (pin "27") (pinfunction "CAGE_27") (pintype "power_in"))
      (node (ref "CageBot2") (pin "28") (pinfunction "CAGE_28") (pintype "power_in"))
      (node (ref "CageBot2") (pin "29") (pinfunction "CAGE_29") (pintype "power_in"))
      (node (ref "CageBot2") (pin "30") (pinfunction "CAGE_30") (pintype "power_in"))
      (node (ref "CageBot2") (pin "31") (pinfunction "CAGE_31") (pintype "power_in"))
      (node (ref "IC16") (pin "10") (pinfunction "GND_10") (pintype "power_in"))
      (node (ref "IC16") (pin "14") (pinfunction "~{OE}_14") (pintype "input"))
      (node (ref "IC16") (pin "15") (pinfunction "GND_15") (pintype "power_in"))
      (node (ref "IC16") (pin "17") (pinfunction "CLKBA_17") (pintype "input"))
      (node (ref "IC16") (pin "21") (pinfunction "GND_21") (pintype "power_in"))
      (node (ref "IC16") (pin "28") (pinfunction "GND_28") (pintype "power_in"))
      (node (ref "IC16") (pin "32") (pinfunction "CLKAB_32") (pintype "input"))
      (node (ref "IC16") (pin "34") (pinfunction "GND_34") (pintype "power_in"))
      (node (ref "IC16") (pin "39") (pinfunction "GND_39") (pintype "power_in"))
      (node (ref "IC16") (pin "4") (pinfunction "GND_4") (pintype "power_in"))
      (node (ref "IC16") (pin "45") (pinfunction "GND_45") (pintype "input"))
      (node (ref "IC20") (pin "2") (pinfunction "GND_2") (pintype "power_in"))
      (node (ref "J4") (pin "1") (pinfunction "VEET_1") (pintype "power_in"))
      (node (ref "J4") (pin "10") (pinfunction "VEER_10") (pintype "power_in"))
      (node (ref "J4") (pin "11") (pinfunction "VEER_11") (pintype "power_in"))
      (node (ref "J4") (pin "14") (pinfunction "VEER_14") (pintype "power_in"))
      (node (ref "J4") (pin "17") (pinfunction "VEET_17") (pintype "power_in"))
      (node (ref "J4") (pin "20") (pinfunction "VEET_20") (pintype "power_in"))
      (node (ref "J4") (pin "9") (pinfunction "VEER_9") (pintype "power_in"))
      (node (ref "J6") (pin "3") (pinfunction "3_3") (pintype "bidirectional"))
      (node (ref "J7") (pin "3") (pinfunction "3_3") (pintype "bidirectional"))
      (node (ref "PB1") (pin "1") (pinfunction "1_1") (pintype "passive"))
      (node (ref "PB1") (pin "2") (pinfunction "2_2") (pintype "passive"))
      (node (ref "R101") (pin "2") (pinfunction "2_2") (pintype "passive"))
      (node (ref "R103") (pin "2") (pinfunction "2_2") (pintype "passive"))
      (node (ref "R155") (pin "2") (pinfunction "2_2") (pintype "passive"))
      (node (ref "R156") (pin "2") (pinfunction "2_2") (pintype "passive"))
      (node (ref "R157") (pin "2") (pinfunction "2_2") (pintype "passive"))
      (node (ref "R158") (pin "2") (pinfunction "2_2") (pintype "passive"))
      (node (ref "R166") (pin "2") (pinfunction "2_2") (pintype "passive"))
      (node (ref "R178") (pin "2") (pinfunction "2_2") (pintype "passive"))
      (node (ref "R186") (pin "2") (pinfunction "2_2") (pintype "passive"))
      (node (ref "R187") (pin "2") (pinfunction "2_2") (pintype "passive"))
      (node (ref "R196") (pin "2") (pinfunction "2_2") (pintype "passive"))
      (node (ref "R197") (pin "2") (pinfunction "2_2") (pintype "passive"))
      (node (ref "R198") (pin "2") (pinfunction "2_2") (pintype "passive"))
      (node (ref "R205") (pin "2") (pinfunction "2_2") (pintype "passive"))
      (node (ref "SW3") (pin "1") (pinfunction "1_1") (pintype "bidirectional"))
      (node (ref "SW3") (pin "2") (pinfunction "2_2") (pintype "bidirectional"))
      (node (ref "SW5") (pin "1") (pinfunction "1_1") (pintype "bidirectional"))
      (node (ref "SW5") (pin "2") (pinfunction "2_2") (pintype "bidirectional"))
      (node (ref "SW6") (pin "1") (pinfunction "1_1") (pintype "bidirectional"))
      (node (ref "SW6") (pin "2") (pinfunction "2_2") (pintype "bidirectional"))
    )
    (net (code "34") (name "Net-(IC16-1B)") (class "Default")
      (node (ref "IC16") (pin "46") (pinfunction "1B_46") (pintype "input"))
      (node (ref "R165") (pin "1") (pinfunction "1_1") (pintype "passive"))
    )
    (net (code "35") (name "Net-(IC16-2B)") (class "Default")
      (node (ref "IC16") (pin "43") (pinfunction "2B_43") (pintype "input"))
      (node (ref "R164") (pin "1") (pinfunction "1_1") (pintype "passive"))
    )
    (net (code "36") (name "Net-(IC16-3B1)") (class "Default")
      (node (ref "IC16") (pin "40") (pinfunction "3B1_40") (pintype "bidirectional"))
      (node (ref "R206") (pin "1") (pinfunction "1_1") (pintype "passive"))
    )
    (net (code "37") (name "Net-(IC16-3B5)") (class "Default")
      (node (ref "IC16") (pin "30") (pinfunction "3B5_30") (pintype "bidirectional"))
      (node (ref "R204") (pin "1") (pinfunction "1_1") (pintype "passive"))
    )
    (net (code "38") (name "Net-(IC20-R)") (class "Default")
      (node (ref "IC20") (pin "5") (pinfunction "R_5") (pintype "output"))
      (node (ref "R109") (pin "1") (pinfunction "1_1") (pintype "passive"))
    )
    (net (code "39") (name "Net-(J4-VCCR)") (class "Default")
      (node (ref "C219") (pin "1") (pinfunction "1_1") (pintype "passive"))
      (node (ref "C228") (pin "1") (pinfunction "1_1") (pintype "passive"))
      (node (ref "J4") (pin "15") (pinfunction "VCCR_15") (pintype "power_in"))
      (node (ref "L11") (pin "2") (pinfunction "2_2") (pintype "passive"))
    )
    (net (code "40") (name "Net-(J4-VCCT)") (class "Default")
      (node (ref "C214") (pin "1") (pinfunction "1_1") (pintype "passive"))
      (node (ref "C220") (pin "1") (pinfunction "1_1") (pintype "passive"))
      (node (ref "J4") (pin "16") (pinfunction "VCCT_16") (pintype "power_in"))
      (node (ref "L5") (pin "2") (pinfunction "2_2") (pintype "passive"))
    )
    (net (code "41") (name "Net-(J6-Pad1)") (class "Default")
      (node (ref "J6") (pin "1") (pinfunction "1_1") (pintype "bidirectional"))
      (node (ref "R155") (pin "1") (pinfunction "1_1") (pintype "passive"))
      (node (ref "R156") (pin "1") (pinfunction "1_1") (pintype "passive"))
      (node (ref "R164") (pin "2") (pinfunction "2_2") (pintype "passive"))
      (node (ref "R178") (pin "1") (pinfunction "1_1") (pintype "passive"))
    )
    (net (code "42") (name "Net-(J6-Pad2)") (class "Default")
      (node (ref "J6") (pin "2") (pinfunction "2_2") (pintype "bidirectional"))
      (node (ref "R157") (pin "1") (pinfunction "1_1") (pintype "passive"))
      (node (ref "R158") (pin "1") (pinfunction "1_1") (pintype "passive"))
      (node (ref "R165") (pin "2") (pinfunction "2_2") (pintype "passive"))
      (node (ref "R166") (pin "1") (pinfunction "1_1") (pintype "passive"))
    )
    (net (code "43") (name "Net-(J7-Pad1)") (class "Default")
      (node (ref "J7") (pin "1") (pinfunction "1_1") (pintype "bidirectional"))
      (node (ref "R186") (pin "1") (pinfunction "1_1") (pintype "passive"))
      (node (ref "R196") (pin "1") (pinfunction "1_1") (pintype "passive"))
      (node (ref "R204") (pin "2") (pinfunction "2_2") (pintype "passive"))
      (node (ref "R205") (pin "1") (pinfunction "1_1") (pintype "passive"))
    )
    (net (code "44") (name "Net-(J7-Pad2)") (class "Default")
      (node (ref "J7") (pin "2") (pinfunction "2_2") (pintype "bidirectional"))
      (node (ref "R187") (pin "1") (pinfunction "1_1") (pintype "passive"))
      (node (ref "R197") (pin "1") (pinfunction "1_1") (pintype "passive"))
      (node (ref "R198") (pin "1") (pinfunction "1_1") (pintype "passive"))
      (node (ref "R206") (pin "2") (pinfunction "2_2") (pintype "passive"))
    )
    (net (code "45") (name "Net-(LD24A-A)") (class "Default")
      (node (ref "LD24") (pin "2") (pinfunction "A_2") (pintype "passive"))
      (node (ref "R82") (pin "2") (pinfunction "2_2") (pintype "passive"))
    )
    (net (code "46") (name "Net-(LD24B-A)") (class "Default")
      (node (ref "LD24") (pin "4") (pinfunction "A_4") (pintype "passive"))
      (node (ref "R83") (pin "2") (pinfunction "2_2") (pintype "passive"))
    )
    (net (code "47") (name "Net-(LD24C-A)") (class "Default")
      (node (ref "LD24") (pin "6") (pinfunction "A_6") (pintype "passive"))
      (node (ref "R89") (pin "2") (pinfunction "2_2") (pintype "passive"))
    )
    (net (code "48") (name "Net-(LD24D-A)") (class "Default")
      (node (ref "LD24") (pin "8") (pinfunction "A_8") (pintype "passive"))
      (node (ref "R95") (pin "2") (pinfunction "2_2") (pintype "passive"))
    )
    (net (code "49") (name "Net-(LD25A-A)") (class "Default")
      (node (ref "LD25") (pin "2") (pinfunction "A_2") (pintype "passive"))
      (node (ref "R96") (pin "2") (pinfunction "2_2") (pintype "passive"))
    )
    (net (code "50") (name "Net-(LD25B-A)") (class "Default")
      (node (ref "LD25") (pin "4") (pinfunction "A_4") (pintype "passive"))
      (node (ref "R98") (pin "2") (pinfunction "2_2") (pintype "passive"))
    )
    (net (code "51") (name "Net-(LD25C-A)") (class "Default")
      (node (ref "LD25") (pin "6") (pinfunction "A_6") (pintype "passive"))
      (node (ref "R99") (pin "2") (pinfunction "2_2") (pintype "passive"))
    )
    (net (code "52") (name "Net-(LD25D-A)") (class "Default")
      (node (ref "LD25") (pin "8") (pinfunction "A_8") (pintype "passive"))
      (node (ref "R100") (pin "2") (pinfunction "2_2") (pintype "passive"))
    )
    (net (code "53") (name "Net-(R101-Pad1)") (class "Default")
      (node (ref "R101") (pin "1") (pinfunction "1_1") (pintype "passive"))
      (node (ref "TP2") (pin "1") (pinfunction "1_1") (pintype "bidirectional"))
    )
    (net (code "54") (name "Net-(R102-Pad1)") (class "Default")
      (node (ref "R102") (pin "1") (pinfunction "1_1") (pintype "passive"))
      (node (ref "TP1") (pin "1") (pinfunction "1_1") (pintype "bidirectional"))
    )
    (net (code "55") (name "Net-(R102-Pad2)") (class "Default")
      (node (ref "R102") (pin "2") (pinfunction "2_2") (pintype "passive"))
      (node (ref "TP3") (pin "1") (pinfunction "1_1") (pintype "bidirectional"))
    )
    (net (code "56") (name "Net-(R103-Pad1)") (class "Default")
      (node (ref "R103") (pin "1") (pinfunction "1_1") (pintype "passive"))
      (node (ref "TP5") (pin "1") (pinfunction "1_1") (pintype "bidirectional"))
    )
    (net (code "57") (name "Net-(R104-Pad1)") (class "Default")
      (node (ref "R104") (pin "1") (pinfunction "1_1") (pintype "passive"))
      (node (ref "TP4") (pin "1") (pinfunction "1_1") (pintype "bidirectional"))
    )
    (net (code "58") (name "Net-(R104-Pad2)") (class "Default")
      (node (ref "R104") (pin "2") (pinfunction "2_2") (pintype "passive"))
      (node (ref "TP6") (pin "1") (pinfunction "1_1") (pintype "bidirectional"))
    )
    (net (code "59") (name "P3V3") (class "Default")
      (node (ref "C13") (pin "1") (pinfunction "1_1") (pintype "passive"))
      (node (ref "C186") (pin "1") (pinfunction "1_1") (pintype "passive"))
      (node (ref "C202") (pin "2") (pinfunction "2_2") (pintype "passive"))
      (node (ref "C297") (pin "2") (pinfunction "2_2") (pintype "passive"))
      (node (ref "C306") (pin "1") (pinfunction "1_1") (pintype "passive"))
      (node (ref "C307") (pin "1") (pinfunction "1_1") (pintype "passive"))
      (node (ref "C314") (pin "1") (pinfunction "1_1") (pintype "passive"))
      (node (ref "C315") (pin "2") (pinfunction "2_2") (pintype "passive"))
      (node (ref "C320") (pin "2") (pinfunction "2_2") (pintype "passive"))
      (node (ref "IC16") (pin "11") (pinfunction "LE_11") (pintype "input"))
      (node (ref "IC16") (pin "18") (pinfunction "VCC_18") (pintype "power_in"))
      (node (ref "IC16") (pin "25") (pinfunction "VCC_25") (pintype "power_in"))
      (node (ref "IC16") (pin "31") (pinfunction "VCC_31") (pintype "power_in"))
      (node (ref "IC16") (pin "35") (pinfunction "VCC_35") (pintype "power_in"))
      (node (ref "IC16") (pin "38") (pinfunction "VCC_38") (pintype "power_in"))
      (node (ref "IC16") (pin "42") (pinfunction "VCC_42") (pintype "power_in"))
      (node (ref "IC16") (pin "44") (pinfunction "BIASVCC_44") (pintype "input"))
      (node (ref "IC16") (pin "47") (pinfunction "VCC_47") (pintype "input"))
      (node (ref "IC16") (pin "7") (pinfunction "VCC_7") (pintype "power_in"))
      (node (ref "IC20") (pin "1") (pinfunction "VCC_1") (pintype "power_in"))
      (node (ref "L11") (pin "1") (pinfunction "1_1") (pintype "passive"))
      (node (ref "L5") (pin "1") (pinfunction "1_1") (pintype "passive"))
      (node (ref "R100") (pin "1") (pinfunction "1_1") (pintype "passive"))
      (node (ref "R400") (pin "2") (pinfunction "2_2") (pintype "passive"))
      (node (ref "R401") (pin "2") (pinfunction "2_2") (pintype "passive"))
      (node (ref "R402") (pin "2") (pinfunction "2_2") (pintype "passive"))
      (node (ref "R403") (pin "2") (pinfunction "2_2") (pintype "passive"))
      (node (ref "R404") (pin "2") (pinfunction "2_2") (pintype "passive"))
      (node (ref "R82") (pin "1") (pinfunction "1_1") (pintype "passive"))
      (node (ref "R83") (pin "1") (pinfunction "1_1") (pintype "passive"))
      (node (ref "R86") (pin "1") (pinfunction "1_1") (pintype "passive"))
      (node (ref "R89") (pin "1") (pinfunction "1_1") (pintype "passive"))
      (node (ref "R95") (pin "1") (pinfunction "1_1") (pintype "passive"))
      (node (ref "R96") (pin "1") (pinfunction "1_1") (pintype "passive"))
      (node (ref "R98") (pin "1") (pinfunction "1_1") (pintype "passive"))
      (node (ref "R99") (pin "1") (pinfunction "1_1") (pintype "passive"))
    )
    (net (code "60") (name "unconnected-(IC16-3A2-Pad12)") (class "Default")
      (node (ref "IC16") (pin "12") (pinfunction "3A2_12") (pintype "bidirectional"))
    )
    (net (code "61") (name "unconnected-(IC16-3A3-Pad13)") (class "Default")
      (node (ref "IC16") (pin "13") (pinfunction "3A3_13") (pintype "bidirectional"))
    )
    (net (code "62") (name "unconnected-(IC16-3A4-Pad16)") (class "Default")
      (node (ref "IC16") (pin "16") (pinfunction "3A4_16") (pintype "bidirectional"))
    )
    (net (code "63") (name "unconnected-(IC16-3A6-Pad20)") (class "Default")
      (node (ref "IC16") (pin "20") (pinfunction "3A6_20") (pintype "bidirectional"))
    )
    (net (code "64") (name "unconnected-(IC16-3A7-Pad22)") (class "Default")
      (node (ref "IC16") (pin "22") (pinfunction "3A7_22") (pintype "bidirectional"))
    )
    (net (code "65") (name "unconnected-(IC16-3A8-Pad23)") (class "Default")
      (node (ref "IC16") (pin "23") (pinfunction "3A8_23") (pintype "bidirectional"))
    )
    (net (code "66") (name "unconnected-(IC16-3B2-Pad37)") (class "Default")
      (node (ref "IC16") (pin "37") (pinfunction "3B2_37") (pintype "bidirectional"))
    )
    (net (code "67") (name "unconnected-(IC16-3B3-Pad36)") (class "Default")
      (node (ref "IC16") (pin "36") (pinfunction "3B3_36") (pintype "bidirectional"))
    )
    (net (code "68") (name "unconnected-(IC16-3B4-Pad33)") (class "Default")
      (node (ref "IC16") (pin "33") (pinfunction "3B4_33") (pintype "bidirectional"))
    )
    (net (code "69") (name "unconnected-(IC16-3B6-Pad29)") (class "Default")
      (node (ref "IC16") (pin "29") (pinfunction "3B6_29") (pintype "bidirectional"))
    )
    (net (code "70") (name "unconnected-(IC16-3B7-Pad27)") (class "Default")
      (node (ref "IC16") (pin "27") (pinfunction "3B7_27") (pintype "bidirectional"))
    )
    (net (code "71") (name "unconnected-(IC16-3B8-Pad26)") (class "Default")
      (node (ref "IC16") (pin "26") (pinfunction "3B8_26") (pintype "bidirectional"))
    )
  )
)
